# ProDoc_Schematic1_2025-11-01.net
KiCad netlist of a schematic drawn in EasyEDA Pro
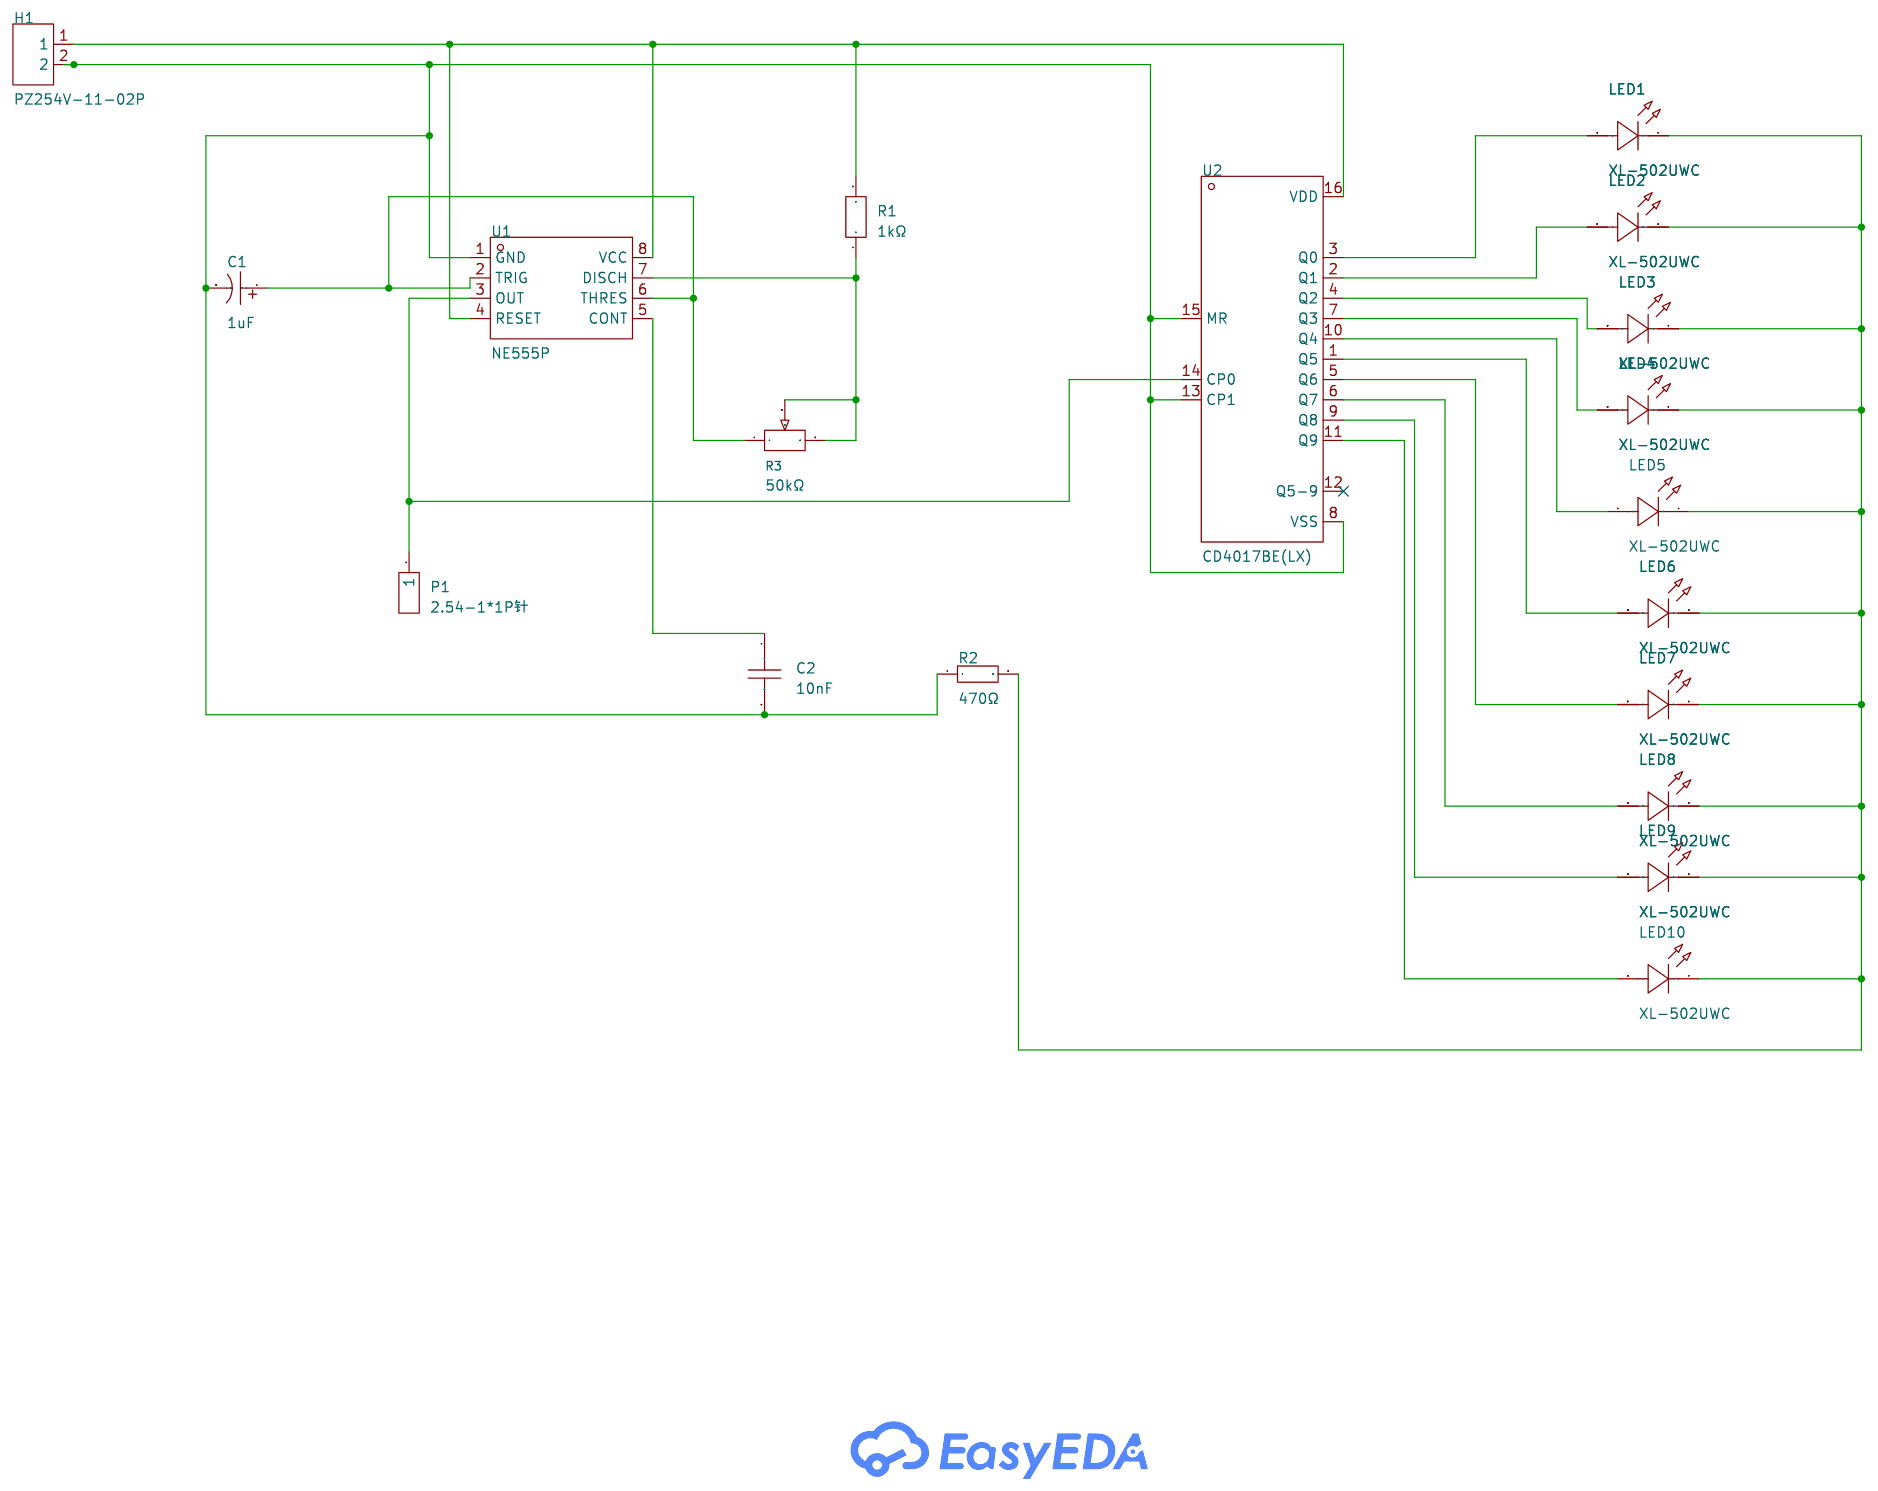
[diagram p0: schematic sheet]

(export (version "E")
  (design (tool "Eeschema 10.0.6"))
  (components
    (comp (ref "C1")
      (value "1uF")
      (footprint "easyedapro:CAP-TH_BD5.0-P2.00-D0.8-FD")
      (fields (field (name "Manufacturer Part") "KF010M050C110A") (field (name "Manufacturer") "CapXon(丰宾)"))
      (libsource (lib "easyedapro") (part "KF010M050C110A"))
    )
    (comp (ref "C2")
      (value "10nF")
      (footprint "easyedapro:CAP-TH_L8.0-W4.0-P5.00-D1.2")
      (fields (field (name "Manufacturer Part") "N09F1B103MN0B0S0N0") (field (name "Manufacturer") "STE(松田)"))
      (libsource (lib "easyedapro") (part "N09F1B103MN0B0S0N0"))
    )
    (comp (ref "H1")
      (value "PZ254V-11-02P")
      (footprint "easyedapro:HDR-TH_2P-P2.54-V-M")
      (fields (field (name "Manufacturer") "XFCN(兴飞)"))
      (libsource (lib "easyedapro") (part "PZ254V-11-02P"))
    )
    (comp (ref "LED1")
      (value "XL-502UWC")
      (footprint "easyedapro:LED-TH_BD5.9-P2.54-RD_WHITE")
      (fields (field (name "Manufacturer") "XINGLIGHT(成兴光)"))
      (libsource (lib "easyedapro") (part "XL-502UWC"))
    )
    (comp (ref "LED2")
      (value "XL-502UWC")
      (footprint "easyedapro:LED-TH_BD5.9-P2.54-RD_WHITE")
      (fields (field (name "Manufacturer") "XINGLIGHT(成兴光)"))
      (libsource (lib "easyedapro") (part "XL-502UWC"))
    )
    (comp (ref "LED3")
      (value "XL-502UWC")
      (footprint "easyedapro:LED-TH_BD5.9-P2.54-RD_WHITE")
      (fields (field (name "Manufacturer") "XINGLIGHT(成兴光)"))
      (libsource (lib "easyedapro") (part "XL-502UWC"))
    )
    (comp (ref "LED4")
      (value "XL-502UWC")
      (footprint "easyedapro:LED-TH_BD5.9-P2.54-RD_WHITE")
      (fields (field (name "Manufacturer") "XINGLIGHT(成兴光)"))
      (libsource (lib "easyedapro") (part "XL-502UWC"))
    )
    (comp (ref "LED5")
      (value "XL-502UWC")
      (footprint "easyedapro:LED-TH_BD5.9-P2.54-RD_WHITE")
      (fields (field (name "Manufacturer") "XINGLIGHT(成兴光)"))
      (libsource (lib "easyedapro") (part "XL-502UWC"))
    )
    (comp (ref "LED6")
      (value "XL-502UWC")
      (footprint "easyedapro:LED-TH_BD5.9-P2.54-RD_WHITE")
      (fields (field (name "Manufacturer") "XINGLIGHT(成兴光)"))
      (libsource (lib "easyedapro") (part "XL-502UWC"))
    )
    (comp (ref "LED7")
      (value "XL-502UWC")
      (footprint "easyedapro:LED-TH_BD5.9-P2.54-RD_WHITE")
      (fields (field (name "Manufacturer") "XINGLIGHT(成兴光)"))
      (libsource (lib "easyedapro") (part "XL-502UWC"))
    )
    (comp (ref "LED8")
      (value "XL-502UWC")
      (footprint "easyedapro:LED-TH_BD5.9-P2.54-RD_WHITE")
      (fields (field (name "Manufacturer") "XINGLIGHT(成兴光)"))
      (libsource (lib "easyedapro") (part "XL-502UWC"))
    )
    (comp (ref "LED9")
      (value "XL-502UWC")
      (footprint "easyedapro:LED-TH_BD5.9-P2.54-RD_WHITE")
      (fields (field (name "Manufacturer") "XINGLIGHT(成兴光)"))
      (libsource (lib "easyedapro") (part "XL-502UWC"))
    )
    (comp (ref "LED10")
      (value "XL-502UWC")
      (footprint "easyedapro:LED-TH_BD5.9-P2.54-RD_WHITE")
      (fields (field (name "Manufacturer") "XINGLIGHT(成兴光)"))
      (libsource (lib "easyedapro") (part "XL-502UWC"))
    )
    (comp (ref "P1")
      (value "2.54-1*1P针")
      (footprint "easyedapro:HDR-TH_1P-P2.54-V-M")
      (fields (field (name "Manufacturer") "BOOMELE(博穆精密)"))
      (libsource (lib "easyedapro") (part "Header-Male-2.54_1x1"))
    )
    (comp (ref "R1")
      (value "1kΩ")
      (footprint "easyedapro:RES-TH_BD2.3-L6.5-P10.50-D0.5")
      (fields (field (name "Manufacturer Part") "MF1/4W-1KΩ±1%T52") (field (name "Manufacturer") "华星机电"))
      (libsource (lib "easyedapro") (part "MF1/4W-1KΩ±1%T52"))
    )
    (comp (ref "R2")
      (value "470Ω")
      (footprint "easyedapro:RES-TH_BD2.2-L6.5-P10.50-D0.6")
      (fields
        (field (name "Manufacturer Part") "MFR0W4F4700A50")
        (field (name "Manufacturer") "UNI-ROYAL(厚声)")
      )
      (libsource (lib "easyedapro") (part "MFR0W4F4700A50"))
    )
    (comp (ref "R3")
      (value "50kΩ")
      (footprint "easyedapro:RES-ADJ-TH_3P-L9.5-W4.85-P2.50-BL-L")
      (fields (field (name "Manufacturer Part") "3296X-1-503") (field (name "Manufacturer") "BOCHEN(博晨)"))
      (libsource (lib "easyedapro") (part "3296X-1-503_C118912"))
    )
    (comp (ref "U1")
      (value "NE555P")
      (footprint "easyedapro:DIP-8_L9.8-W6.6-P2.54-LS7.6-BL")
      (fields (field (name "Manufacturer") "TI(德州仪器)"))
      (libsource (lib "easyedapro") (part "NE555P"))
    )
    (comp (ref "U2")
      (value "CD4017BE(LX)")
      (footprint "easyedapro:PDIP-16_L19.3-W6.4-P2.54-LS7.94-BL")
      (fields (field (name "Manufacturer") "LX(灵星芯微)"))
      (libsource (lib "easyedapro") (part "CD4017BE(LX)"))
    )
  )
  (nets
    (net (code "1") (name "Net-(LED1-A)") (class "Default")
      (node (ref "LED1") (pin "2") (pinfunction "A_2") (pintype "unspecified"))
      (node (ref "U2") (pin "3") (pinfunction "Q0_3") (pintype "unspecified"))
    )
    (net (code "2") (name "Net-(LED1-K)") (class "Default")
      (node (ref "LED1") (pin "1") (pinfunction "K_1") (pintype "unspecified"))
      (node (ref "LED10") (pin "1") (pinfunction "K_1") (pintype "unspecified"))
      (node (ref "LED2") (pin "1") (pinfunction "K_1") (pintype "unspecified"))
      (node (ref "LED3") (pin "1") (pinfunction "K_1") (pintype "unspecified"))
      (node (ref "LED4") (pin "1") (pinfunction "K_1") (pintype "unspecified"))
      (node (ref "LED5") (pin "1") (pinfunction "K_1") (pintype "unspecified"))
      (node (ref "LED6") (pin "1") (pinfunction "K_1") (pintype "unspecified"))
      (node (ref "LED7") (pin "1") (pinfunction "K_1") (pintype "unspecified"))
      (node (ref "LED8") (pin "1") (pinfunction "K_1") (pintype "unspecified"))
      (node (ref "LED9") (pin "1") (pinfunction "K_1") (pintype "unspecified"))
      (node (ref "R2") (pin "2") (pinfunction "2_2") (pintype "input"))
    )
    (net (code "3") (name "Net-(LED2-A)") (class "Default")
      (node (ref "LED2") (pin "2") (pinfunction "A_2") (pintype "unspecified"))
      (node (ref "U2") (pin "2") (pinfunction "Q1_2") (pintype "unspecified"))
    )
    (net (code "4") (name "Net-(LED3-A)") (class "Default")
      (node (ref "LED3") (pin "2") (pinfunction "A_2") (pintype "unspecified"))
      (node (ref "U2") (pin "4") (pinfunction "Q2_4") (pintype "unspecified"))
    )
    (net (code "5") (name "Net-(LED4-A)") (class "Default")
      (node (ref "LED4") (pin "2") (pinfunction "A_2") (pintype "unspecified"))
      (node (ref "U2") (pin "7") (pinfunction "Q3_7") (pintype "unspecified"))
    )
    (net (code "6") (name "Net-(LED5-A)") (class "Default")
      (node (ref "LED5") (pin "2") (pinfunction "A_2") (pintype "unspecified"))
      (node (ref "U2") (pin "10") (pinfunction "Q4_10") (pintype "unspecified"))
    )
    (net (code "7") (name "Net-(LED6-A)") (class "Default")
      (node (ref "LED6") (pin "2") (pinfunction "A_2") (pintype "unspecified"))
      (node (ref "U2") (pin "1") (pinfunction "Q5_1") (pintype "unspecified"))
    )
    (net (code "8") (name "Net-(LED7-A)") (class "Default")
      (node (ref "LED7") (pin "2") (pinfunction "A_2") (pintype "unspecified"))
      (node (ref "U2") (pin "5") (pinfunction "Q6_5") (pintype "unspecified"))
    )
    (net (code "9") (name "Net-(LED8-A)") (class "Default")
      (node (ref "LED8") (pin "2") (pinfunction "A_2") (pintype "unspecified"))
      (node (ref "U2") (pin "6") (pinfunction "Q7_6") (pintype "unspecified"))
    )
    (net (code "10") (name "Net-(LED9-A)") (class "Default")
      (node (ref "LED9") (pin "2") (pinfunction "A_2") (pintype "unspecified"))
      (node (ref "U2") (pin "9") (pinfunction "Q8_9") (pintype "unspecified"))
    )
    (net (code "11") (name "Net-(LED10-A)") (class "Default")
      (node (ref "LED10") (pin "2") (pinfunction "A_2") (pintype "unspecified"))
      (node (ref "U2") (pin "11") (pinfunction "Q9_11") (pintype "unspecified"))
    )
    (net (code "12") (name "Net-(U1-CONT)") (class "Default")
      (node (ref "C2") (pin "1") (pinfunction "1_1") (pintype "unspecified"))
      (node (ref "U1") (pin "5") (pinfunction "CONT_5") (pintype "input"))
    )
    (net (code "13") (name "Net-(U1-DISCH)") (class "Default")
      (node (ref "R1") (pin "1") (pinfunction "1_1") (pintype "unspecified"))
      (node (ref "R3") (pin "2") (pinfunction "2_2") (pintype "input"))
      (node (ref "R3") (pin "3") (pinfunction "3_3") (pintype "input"))
      (node (ref "U1") (pin "7") (pinfunction "DISCH_7") (pintype "input"))
    )
    (net (code "14") (name "Net-(U1-GND)") (class "Default")
      (node (ref "C1") (pin "2") (pinfunction "2_2") (pintype "input"))
      (node (ref "C2") (pin "2") (pinfunction "2_2") (pintype "unspecified"))
      (node (ref "H1") (pin "2") (pinfunction "2_2") (pintype "unspecified"))
      (node (ref "R2") (pin "1") (pinfunction "1_1") (pintype "input"))
      (node (ref "U1") (pin "1") (pinfunction "GND_1") (pintype "input"))
      (node (ref "U2") (pin "13") (pinfunction "CP1_13") (pintype "unspecified"))
      (node (ref "U2") (pin "15") (pinfunction "MR_15") (pintype "unspecified"))
      (node (ref "U2") (pin "8") (pinfunction "VSS_8") (pintype "unspecified"))
    )
    (net (code "15") (name "Net-(U1-OUT)") (class "Default")
      (node (ref "P1") (pin "1") (pinfunction "1_1") (pintype "input"))
      (node (ref "U1") (pin "3") (pinfunction "OUT_3") (pintype "input"))
      (node (ref "U2") (pin "14") (pinfunction "CP0_14") (pintype "unspecified"))
    )
    (net (code "16") (name "Net-(U1-RESET)") (class "Default")
      (node (ref "H1") (pin "1") (pinfunction "1_1") (pintype "unspecified"))
      (node (ref "R1") (pin "2") (pinfunction "2_2") (pintype "unspecified"))
      (node (ref "U1") (pin "4") (pinfunction "RESET_4") (pintype "input"))
      (node (ref "U1") (pin "8") (pinfunction "VCC_8") (pintype "input"))
      (node (ref "U2") (pin "16") (pinfunction "VDD_16") (pintype "unspecified"))
    )
    (net (code "17") (name "Net-(U1-THRES)") (class "Default")
      (node (ref "C1") (pin "1") (pinfunction "1_1") (pintype "input"))
      (node (ref "R3") (pin "1") (pinfunction "1_1") (pintype "input"))
      (node (ref "U1") (pin "2") (pinfunction "TRIG_2") (pintype "input"))
      (node (ref "U1") (pin "6") (pinfunction "THRES_6") (pintype "input"))
    )
    (net (code "18") (name "unconnected-(U2-Q5-9-Pad12)") (class "Default")
      (node (ref "U2") (pin "12") (pinfunction "Q5-9_12") (pintype "unspecified+no_connect"))
    )
  )
)
